# bluesmirf.net
KiCad netlist of a schematic drawn in EAGLE
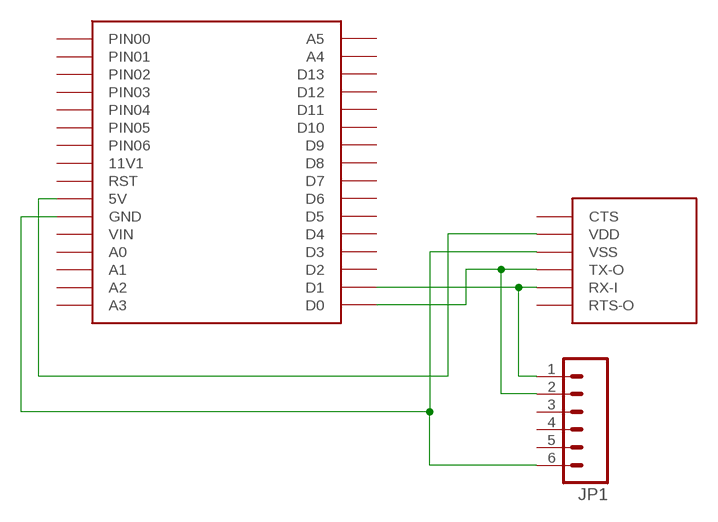
[diagram p0: schematic, sheet 1]
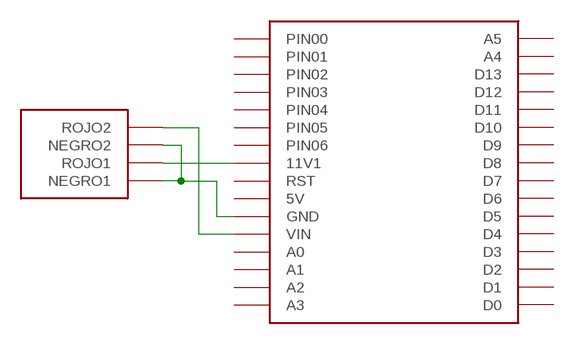
[diagram p1: schematic, sheet 2]
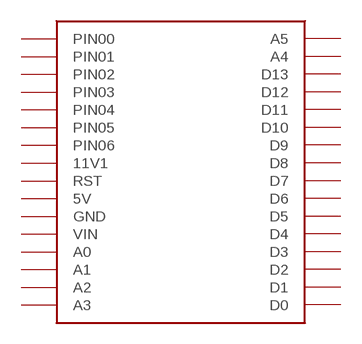
[diagram p2: schematic, sheet 3]

(export (version "E")
  (design (tool "Eeschema 10.0.6"))
  (components
    (comp (ref "U$7")
      (value "BASE-FINAL")
      (footprint "eagle-import:BASE-FINAL")
      (libsource (lib "eagle-import") (part "BASE-FINAL"))
    )
    (comp (ref "U$3")
      (value "BASE-FINAL")
      (footprint "eagle-import:BASE-FINAL")
      (libsource (lib "eagle-import") (part "BASE-FINAL"))
    )
    (comp (ref "U$4")
      (value "CONECTOR_AUDIO")
      (footprint "eagle-import:CONECTOR_AUDIO")
      (libsource (lib "eagle-import") (part "CONECTOR_AUDIO"))
    )
    (comp (ref "JP1")
      (value "M06LONGPADS")
      (footprint "eagle-import:1X06_LONGPADS")
      (libsource (lib "eagle-import") (part "M06LONGPADS"))
    )
    (comp (ref "U$1")
      (value "BASE-FINAL")
      (footprint "eagle-import:BASE-FINAL")
      (libsource (lib "eagle-import") (part "BASE-FINAL"))
    )
    (comp (ref "U$2")
      (value "BLUESMIRF")
      (footprint "eagle-import:BLUESMIRF")
      (libsource (lib "eagle-import") (part "BLUESMIRF"))
    )
  )
  (nets
    (net (code "1") (name "Net-(JP1-Pad6)") (class "Default")
      (node (ref "JP1") (pin "6") (pinfunction "6_6") (pintype "passive"))
      (node (ref "U$1") (pin "GND") (pinfunction "GND_GND") (pintype "bidirectional"))
      (node (ref "U$2") (pin "VSS") (pinfunction "VSS_VSS") (pintype "power_in"))
    )
    (net (code "2") (name "Net-(U$1-D0)") (class "Default")
      (node (ref "JP1") (pin "2") (pinfunction "2_2") (pintype "passive"))
      (node (ref "U$1") (pin "0") (pinfunction "D0_0") (pintype "bidirectional"))
      (node (ref "U$2") (pin "TX-O") (pinfunction "TX-O_TX-O") (pintype "output"))
    )
    (net (code "3") (name "Net-(U$1-D1)") (class "Default")
      (node (ref "JP1") (pin "1") (pinfunction "1_1") (pintype "passive"))
      (node (ref "U$1") (pin "1") (pinfunction "D1_1") (pintype "bidirectional"))
      (node (ref "U$2") (pin "RX-I") (pinfunction "RX-I_RX-I") (pintype "input"))
    )
    (net (code "4") (name "Net-(U$1-Pad5V)") (class "Default")
      (node (ref "U$1") (pin "5V") (pinfunction "5V_5V") (pintype "bidirectional"))
      (node (ref "U$2") (pin "VDD") (pinfunction "VDD_VDD") (pintype "power_in"))
    )
    (net (code "5") (name "Net-(U$3-11V1)") (class "Default")
      (node (ref "U$3") (pin "12V") (pinfunction "11V1_12V") (pintype "bidirectional"))
      (node (ref "U$4") (pin "ROJO1") (pinfunction "ROJO1_ROJO1") (pintype "bidirectional"))
    )
    (net (code "6") (name "Net-(U$3-PadGND)") (class "Default")
      (node (ref "U$3") (pin "GND") (pinfunction "GND_GND") (pintype "bidirectional"))
      (node (ref "U$4") (pin "NEGRO1") (pinfunction "NEGRO1_NEGRO1") (pintype "bidirectional"))
      (node (ref "U$4") (pin "NEGRO2") (pinfunction "NEGRO2_NEGRO2") (pintype "bidirectional"))
    )
    (net (code "7") (name "Net-(U$3-PadVIN)") (class "Default")
      (node (ref "U$3") (pin "VIN") (pinfunction "VIN_VIN") (pintype "bidirectional"))
      (node (ref "U$4") (pin "ROJO2") (pinfunction "ROJO2_ROJO2") (pintype "bidirectional"))
    )
    (net (code "8") (name "unconnected-(JP1-Pad3)") (class "Default")
      (node (ref "JP1") (pin "3") (pinfunction "3_3") (pintype "passive"))
    )
    (net (code "9") (name "unconnected-(JP1-Pad4)") (class "Default")
      (node (ref "JP1") (pin "4") (pinfunction "4_4") (pintype "passive"))
    )
    (net (code "10") (name "unconnected-(JP1-Pad5)") (class "Default")
      (node (ref "JP1") (pin "5") (pinfunction "5_5") (pintype "passive"))
    )
    (net (code "11") (name "unconnected-(U$1-11V1-Pad12V)") (class "Default")
      (node (ref "U$1") (pin "12V") (pinfunction "11V1_12V") (pintype "bidirectional"))
    )
    (net (code "12") (name "unconnected-(U$1-D2-Pad2)") (class "Default")
      (node (ref "U$1") (pin "2") (pinfunction "D2_2") (pintype "bidirectional"))
    )
    (net (code "13") (name "unconnected-(U$1-D3-Pad3)") (class "Default")
      (node (ref "U$1") (pin "3") (pinfunction "D3_3") (pintype "bidirectional"))
    )
    (net (code "14") (name "unconnected-(U$1-D4-Pad4)") (class "Default")
      (node (ref "U$1") (pin "4") (pinfunction "D4_4") (pintype "bidirectional"))
    )
    (net (code "15") (name "unconnected-(U$1-D5-Pad5)") (class "Default")
      (node (ref "U$1") (pin "5") (pinfunction "D5_5") (pintype "bidirectional"))
    )
    (net (code "16") (name "unconnected-(U$1-D6-Pad6)") (class "Default")
      (node (ref "U$1") (pin "6") (pinfunction "D6_6") (pintype "bidirectional"))
    )
    (net (code "17") (name "unconnected-(U$1-D7-Pad7)") (class "Default")
      (node (ref "U$1") (pin "7") (pinfunction "D7_7") (pintype "bidirectional"))
    )
    (net (code "18") (name "unconnected-(U$1-D8-Pad8)") (class "Default")
      (node (ref "U$1") (pin "8") (pinfunction "D8_8") (pintype "bidirectional"))
    )
    (net (code "19") (name "unconnected-(U$1-D9-Pad9)") (class "Default")
      (node (ref "U$1") (pin "9") (pinfunction "D9_9") (pintype "bidirectional"))
    )
    (net (code "20") (name "unconnected-(U$1-D10-Pad10)") (class "Default")
      (node (ref "U$1") (pin "10") (pinfunction "D10_10") (pintype "bidirectional"))
    )
    (net (code "21") (name "unconnected-(U$1-D11-Pad11)") (class "Default")
      (node (ref "U$1") (pin "11") (pinfunction "D11_11") (pintype "bidirectional"))
    )
    (net (code "22") (name "unconnected-(U$1-D12-Pad12)") (class "Default")
      (node (ref "U$1") (pin "12") (pinfunction "D12_12") (pintype "bidirectional"))
    )
    (net (code "23") (name "unconnected-(U$1-D13-Pad13)") (class "Default")
      (node (ref "U$1") (pin "13") (pinfunction "D13_13") (pintype "bidirectional"))
    )
    (net (code "24") (name "unconnected-(U$1-PadA0)") (class "Default")
      (node (ref "U$1") (pin "A0") (pinfunction "A0_A0") (pintype "bidirectional"))
    )
    (net (code "25") (name "unconnected-(U$1-PadA1)") (class "Default")
      (node (ref "U$1") (pin "A1") (pinfunction "A1_A1") (pintype "bidirectional"))
    )
    (net (code "26") (name "unconnected-(U$1-PadA2)") (class "Default")
      (node (ref "U$1") (pin "A2") (pinfunction "A2_A2") (pintype "bidirectional"))
    )
    (net (code "27") (name "unconnected-(U$1-PadA3)") (class "Default")
      (node (ref "U$1") (pin "A3") (pinfunction "A3_A3") (pintype "bidirectional"))
    )
    (net (code "28") (name "unconnected-(U$1-PadA4)") (class "Default")
      (node (ref "U$1") (pin "A4") (pinfunction "A4_A4") (pintype "bidirectional"))
    )
    (net (code "29") (name "unconnected-(U$1-PadA5)") (class "Default")
      (node (ref "U$1") (pin "A5") (pinfunction "A5_A5") (pintype "bidirectional"))
    )
    (net (code "30") (name "unconnected-(U$1-PadPIN00)") (class "Default")
      (node (ref "U$1") (pin "PIN00") (pinfunction "PIN00_PIN00") (pintype "bidirectional"))
    )
    (net (code "31") (name "unconnected-(U$1-PadPIN01)") (class "Default")
      (node (ref "U$1") (pin "PIN01") (pinfunction "PIN01_PIN01") (pintype "bidirectional"))
    )
    (net (code "32") (name "unconnected-(U$1-PadPIN02)") (class "Default")
      (node (ref "U$1") (pin "PIN02") (pinfunction "PIN02_PIN02") (pintype "bidirectional"))
    )
    (net (code "33") (name "unconnected-(U$1-PadPIN03)") (class "Default")
      (node (ref "U$1") (pin "PIN03") (pinfunction "PIN03_PIN03") (pintype "bidirectional"))
    )
    (net (code "34") (name "unconnected-(U$1-PadPIN04)") (class "Default")
      (node (ref "U$1") (pin "PIN04") (pinfunction "PIN04_PIN04") (pintype "bidirectional"))
    )
    (net (code "35") (name "unconnected-(U$1-PadPIN05)") (class "Default")
      (node (ref "U$1") (pin "PIN05") (pinfunction "PIN05_PIN05") (pintype "bidirectional"))
    )
    (net (code "36") (name "unconnected-(U$1-PadPIN06)") (class "Default")
      (node (ref "U$1") (pin "PIN06") (pinfunction "PIN06_PIN06") (pintype "bidirectional"))
    )
    (net (code "37") (name "unconnected-(U$1-PadRST)") (class "Default")
      (node (ref "U$1") (pin "RST") (pinfunction "RST_RST") (pintype "bidirectional"))
    )
    (net (code "38") (name "unconnected-(U$1-PadVIN)") (class "Default")
      (node (ref "U$1") (pin "VIN") (pinfunction "VIN_VIN") (pintype "bidirectional"))
    )
    (net (code "39") (name "unconnected-(U$2-CTS-PadCTS-I)") (class "Default")
      (node (ref "U$2") (pin "CTS-I") (pinfunction "CTS_CTS-I") (pintype "input"))
    )
    (net (code "40") (name "unconnected-(U$2-PadRTS-O)") (class "Default")
      (node (ref "U$2") (pin "RTS-O") (pinfunction "RTS-O_RTS-O") (pintype "output"))
    )
    (net (code "41") (name "unconnected-(U$3-D0-Pad0)") (class "Default")
      (node (ref "U$3") (pin "0") (pinfunction "D0_0") (pintype "bidirectional"))
    )
    (net (code "42") (name "unconnected-(U$3-D1-Pad1)") (class "Default")
      (node (ref "U$3") (pin "1") (pinfunction "D1_1") (pintype "bidirectional"))
    )
    (net (code "43") (name "unconnected-(U$3-D2-Pad2)") (class "Default")
      (node (ref "U$3") (pin "2") (pinfunction "D2_2") (pintype "bidirectional"))
    )
    (net (code "44") (name "unconnected-(U$3-D3-Pad3)") (class "Default")
      (node (ref "U$3") (pin "3") (pinfunction "D3_3") (pintype "bidirectional"))
    )
    (net (code "45") (name "unconnected-(U$3-D4-Pad4)") (class "Default")
      (node (ref "U$3") (pin "4") (pinfunction "D4_4") (pintype "bidirectional"))
    )
    (net (code "46") (name "unconnected-(U$3-D5-Pad5)") (class "Default")
      (node (ref "U$3") (pin "5") (pinfunction "D5_5") (pintype "bidirectional"))
    )
    (net (code "47") (name "unconnected-(U$3-D6-Pad6)") (class "Default")
      (node (ref "U$3") (pin "6") (pinfunction "D6_6") (pintype "bidirectional"))
    )
    (net (code "48") (name "unconnected-(U$3-D7-Pad7)") (class "Default")
      (node (ref "U$3") (pin "7") (pinfunction "D7_7") (pintype "bidirectional"))
    )
    (net (code "49") (name "unconnected-(U$3-D8-Pad8)") (class "Default")
      (node (ref "U$3") (pin "8") (pinfunction "D8_8") (pintype "bidirectional"))
    )
    (net (code "50") (name "unconnected-(U$3-D9-Pad9)") (class "Default")
      (node (ref "U$3") (pin "9") (pinfunction "D9_9") (pintype "bidirectional"))
    )
    (net (code "51") (name "unconnected-(U$3-D10-Pad10)") (class "Default")
      (node (ref "U$3") (pin "10") (pinfunction "D10_10") (pintype "bidirectional"))
    )
    (net (code "52") (name "unconnected-(U$3-D11-Pad11)") (class "Default")
      (node (ref "U$3") (pin "11") (pinfunction "D11_11") (pintype "bidirectional"))
    )
    (net (code "53") (name "unconnected-(U$3-D12-Pad12)") (class "Default")
      (node (ref "U$3") (pin "12") (pinfunction "D12_12") (pintype "bidirectional"))
    )
    (net (code "54") (name "unconnected-(U$3-D13-Pad13)") (class "Default")
      (node (ref "U$3") (pin "13") (pinfunction "D13_13") (pintype "bidirectional"))
    )
    (net (code "55") (name "unconnected-(U$3-Pad5V)") (class "Default")
      (node (ref "U$3") (pin "5V") (pinfunction "5V_5V") (pintype "bidirectional"))
    )
    (net (code "56") (name "unconnected-(U$3-PadA0)") (class "Default")
      (node (ref "U$3") (pin "A0") (pinfunction "A0_A0") (pintype "bidirectional"))
    )
    (net (code "57") (name "unconnected-(U$3-PadA1)") (class "Default")
      (node (ref "U$3") (pin "A1") (pinfunction "A1_A1") (pintype "bidirectional"))
    )
    (net (code "58") (name "unconnected-(U$3-PadA2)") (class "Default")
      (node (ref "U$3") (pin "A2") (pinfunction "A2_A2") (pintype "bidirectional"))
    )
    (net (code "59") (name "unconnected-(U$3-PadA3)") (class "Default")
      (node (ref "U$3") (pin "A3") (pinfunction "A3_A3") (pintype "bidirectional"))
    )
    (net (code "60") (name "unconnected-(U$3-PadA4)") (class "Default")
      (node (ref "U$3") (pin "A4") (pinfunction "A4_A4") (pintype "bidirectional"))
    )
    (net (code "61") (name "unconnected-(U$3-PadA5)") (class "Default")
      (node (ref "U$3") (pin "A5") (pinfunction "A5_A5") (pintype "bidirectional"))
    )
    (net (code "62") (name "unconnected-(U$3-PadPIN00)") (class "Default")
      (node (ref "U$3") (pin "PIN00") (pinfunction "PIN00_PIN00") (pintype "bidirectional"))
    )
    (net (code "63") (name "unconnected-(U$3-PadPIN01)") (class "Default")
      (node (ref "U$3") (pin "PIN01") (pinfunction "PIN01_PIN01") (pintype "bidirectional"))
    )
    (net (code "64") (name "unconnected-(U$3-PadPIN02)") (class "Default")
      (node (ref "U$3") (pin "PIN02") (pinfunction "PIN02_PIN02") (pintype "bidirectional"))
    )
    (net (code "65") (name "unconnected-(U$3-PadPIN03)") (class "Default")
      (node (ref "U$3") (pin "PIN03") (pinfunction "PIN03_PIN03") (pintype "bidirectional"))
    )
    (net (code "66") (name "unconnected-(U$3-PadPIN04)") (class "Default")
      (node (ref "U$3") (pin "PIN04") (pinfunction "PIN04_PIN04") (pintype "bidirectional"))
    )
    (net (code "67") (name "unconnected-(U$3-PadPIN05)") (class "Default")
      (node (ref "U$3") (pin "PIN05") (pinfunction "PIN05_PIN05") (pintype "bidirectional"))
    )
    (net (code "68") (name "unconnected-(U$3-PadPIN06)") (class "Default")
      (node (ref "U$3") (pin "PIN06") (pinfunction "PIN06_PIN06") (pintype "bidirectional"))
    )
    (net (code "69") (name "unconnected-(U$3-PadRST)") (class "Default")
      (node (ref "U$3") (pin "RST") (pinfunction "RST_RST") (pintype "bidirectional"))
    )
    (net (code "70") (name "unconnected-(U$7-11V1-Pad12V)") (class "Default")
      (node (ref "U$7") (pin "12V") (pinfunction "11V1_12V") (pintype "bidirectional"))
    )
    (net (code "71") (name "unconnected-(U$7-D0-Pad0)") (class "Default")
      (node (ref "U$7") (pin "0") (pinfunction "D0_0") (pintype "bidirectional"))
    )
    (net (code "72") (name "unconnected-(U$7-D1-Pad1)") (class "Default")
      (node (ref "U$7") (pin "1") (pinfunction "D1_1") (pintype "bidirectional"))
    )
    (net (code "73") (name "unconnected-(U$7-D2-Pad2)") (class "Default")
      (node (ref "U$7") (pin "2") (pinfunction "D2_2") (pintype "bidirectional"))
    )
    (net (code "74") (name "unconnected-(U$7-D3-Pad3)") (class "Default")
      (node (ref "U$7") (pin "3") (pinfunction "D3_3") (pintype "bidirectional"))
    )
    (net (code "75") (name "unconnected-(U$7-D4-Pad4)") (class "Default")
      (node (ref "U$7") (pin "4") (pinfunction "D4_4") (pintype "bidirectional"))
    )
    (net (code "76") (name "unconnected-(U$7-D5-Pad5)") (class "Default")
      (node (ref "U$7") (pin "5") (pinfunction "D5_5") (pintype "bidirectional"))
    )
    (net (code "77") (name "unconnected-(U$7-D6-Pad6)") (class "Default")
      (node (ref "U$7") (pin "6") (pinfunction "D6_6") (pintype "bidirectional"))
    )
    (net (code "78") (name "unconnected-(U$7-D7-Pad7)") (class "Default")
      (node (ref "U$7") (pin "7") (pinfunction "D7_7") (pintype "bidirectional"))
    )
    (net (code "79") (name "unconnected-(U$7-D8-Pad8)") (class "Default")
      (node (ref "U$7") (pin "8") (pinfunction "D8_8") (pintype "bidirectional"))
    )
    (net (code "80") (name "unconnected-(U$7-D9-Pad9)") (class "Default")
      (node (ref "U$7") (pin "9") (pinfunction "D9_9") (pintype "bidirectional"))
    )
    (net (code "81") (name "unconnected-(U$7-D10-Pad10)") (class "Default")
      (node (ref "U$7") (pin "10") (pinfunction "D10_10") (pintype "bidirectional"))
    )
    (net (code "82") (name "unconnected-(U$7-D11-Pad11)") (class "Default")
      (node (ref "U$7") (pin "11") (pinfunction "D11_11") (pintype "bidirectional"))
    )
    (net (code "83") (name "unconnected-(U$7-D12-Pad12)") (class "Default")
      (node (ref "U$7") (pin "12") (pinfunction "D12_12") (pintype "bidirectional"))
    )
    (net (code "84") (name "unconnected-(U$7-D13-Pad13)") (class "Default")
      (node (ref "U$7") (pin "13") (pinfunction "D13_13") (pintype "bidirectional"))
    )
    (net (code "85") (name "unconnected-(U$7-Pad5V)") (class "Default")
      (node (ref "U$7") (pin "5V") (pinfunction "5V_5V") (pintype "bidirectional"))
    )
    (net (code "86") (name "unconnected-(U$7-PadA0)") (class "Default")
      (node (ref "U$7") (pin "A0") (pinfunction "A0_A0") (pintype "bidirectional"))
    )
    (net (code "87") (name "unconnected-(U$7-PadA1)") (class "Default")
      (node (ref "U$7") (pin "A1") (pinfunction "A1_A1") (pintype "bidirectional"))
    )
    (net (code "88") (name "unconnected-(U$7-PadA2)") (class "Default")
      (node (ref "U$7") (pin "A2") (pinfunction "A2_A2") (pintype "bidirectional"))
    )
    (net (code "89") (name "unconnected-(U$7-PadA3)") (class "Default")
      (node (ref "U$7") (pin "A3") (pinfunction "A3_A3") (pintype "bidirectional"))
    )
    (net (code "90") (name "unconnected-(U$7-PadA4)") (class "Default")
      (node (ref "U$7") (pin "A4") (pinfunction "A4_A4") (pintype "bidirectional"))
    )
    (net (code "91") (name "unconnected-(U$7-PadA5)") (class "Default")
      (node (ref "U$7") (pin "A5") (pinfunction "A5_A5") (pintype "bidirectional"))
    )
    (net (code "92") (name "unconnected-(U$7-PadGND)") (class "Default")
      (node (ref "U$7") (pin "GND") (pinfunction "GND_GND") (pintype "bidirectional"))
    )
    (net (code "93") (name "unconnected-(U$7-PadPIN00)") (class "Default")
      (node (ref "U$7") (pin "PIN00") (pinfunction "PIN00_PIN00") (pintype "bidirectional"))
    )
    (net (code "94") (name "unconnected-(U$7-PadPIN01)") (class "Default")
      (node (ref "U$7") (pin "PIN01") (pinfunction "PIN01_PIN01") (pintype "bidirectional"))
    )
    (net (code "95") (name "unconnected-(U$7-PadPIN02)") (class "Default")
      (node (ref "U$7") (pin "PIN02") (pinfunction "PIN02_PIN02") (pintype "bidirectional"))
    )
    (net (code "96") (name "unconnected-(U$7-PadPIN03)") (class "Default")
      (node (ref "U$7") (pin "PIN03") (pinfunction "PIN03_PIN03") (pintype "bidirectional"))
    )
    (net (code "97") (name "unconnected-(U$7-PadPIN04)") (class "Default")
      (node (ref "U$7") (pin "PIN04") (pinfunction "PIN04_PIN04") (pintype "bidirectional"))
    )
    (net (code "98") (name "unconnected-(U$7-PadPIN05)") (class "Default")
      (node (ref "U$7") (pin "PIN05") (pinfunction "PIN05_PIN05") (pintype "bidirectional"))
    )
    (net (code "99") (name "unconnected-(U$7-PadPIN06)") (class "Default")
      (node (ref "U$7") (pin "PIN06") (pinfunction "PIN06_PIN06") (pintype "bidirectional"))
    )
    (net (code "100") (name "unconnected-(U$7-PadRST)") (class "Default")
      (node (ref "U$7") (pin "RST") (pinfunction "RST_RST") (pintype "bidirectional"))
    )
    (net (code "101") (name "unconnected-(U$7-PadVIN)") (class "Default")
      (node (ref "U$7") (pin "VIN") (pinfunction "VIN_VIN") (pintype "bidirectional"))
    )
  )
)
